# driver.net
KiCad netlist of a schematic drawn in Altium Designer
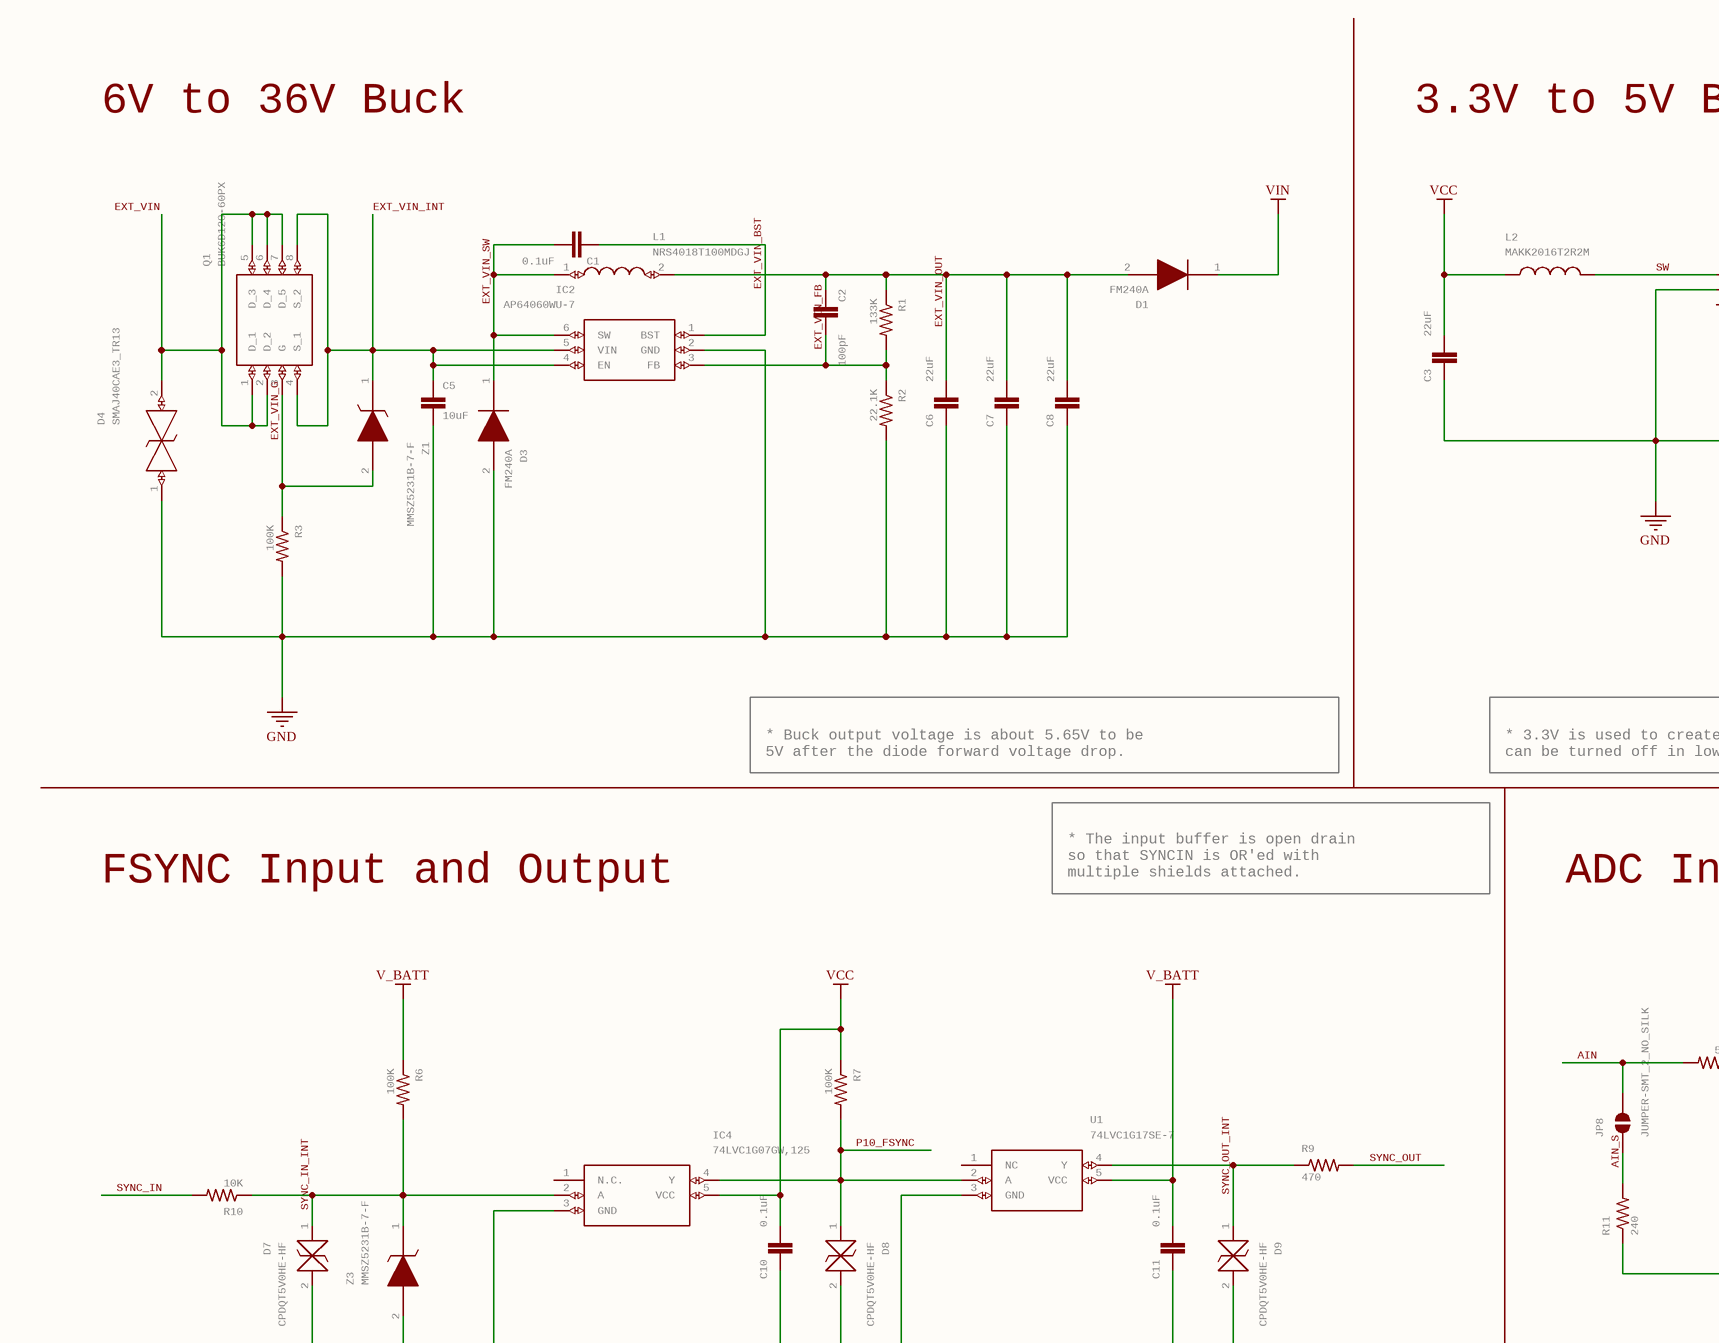
[diagram p0: driver.SchDoc, top left]
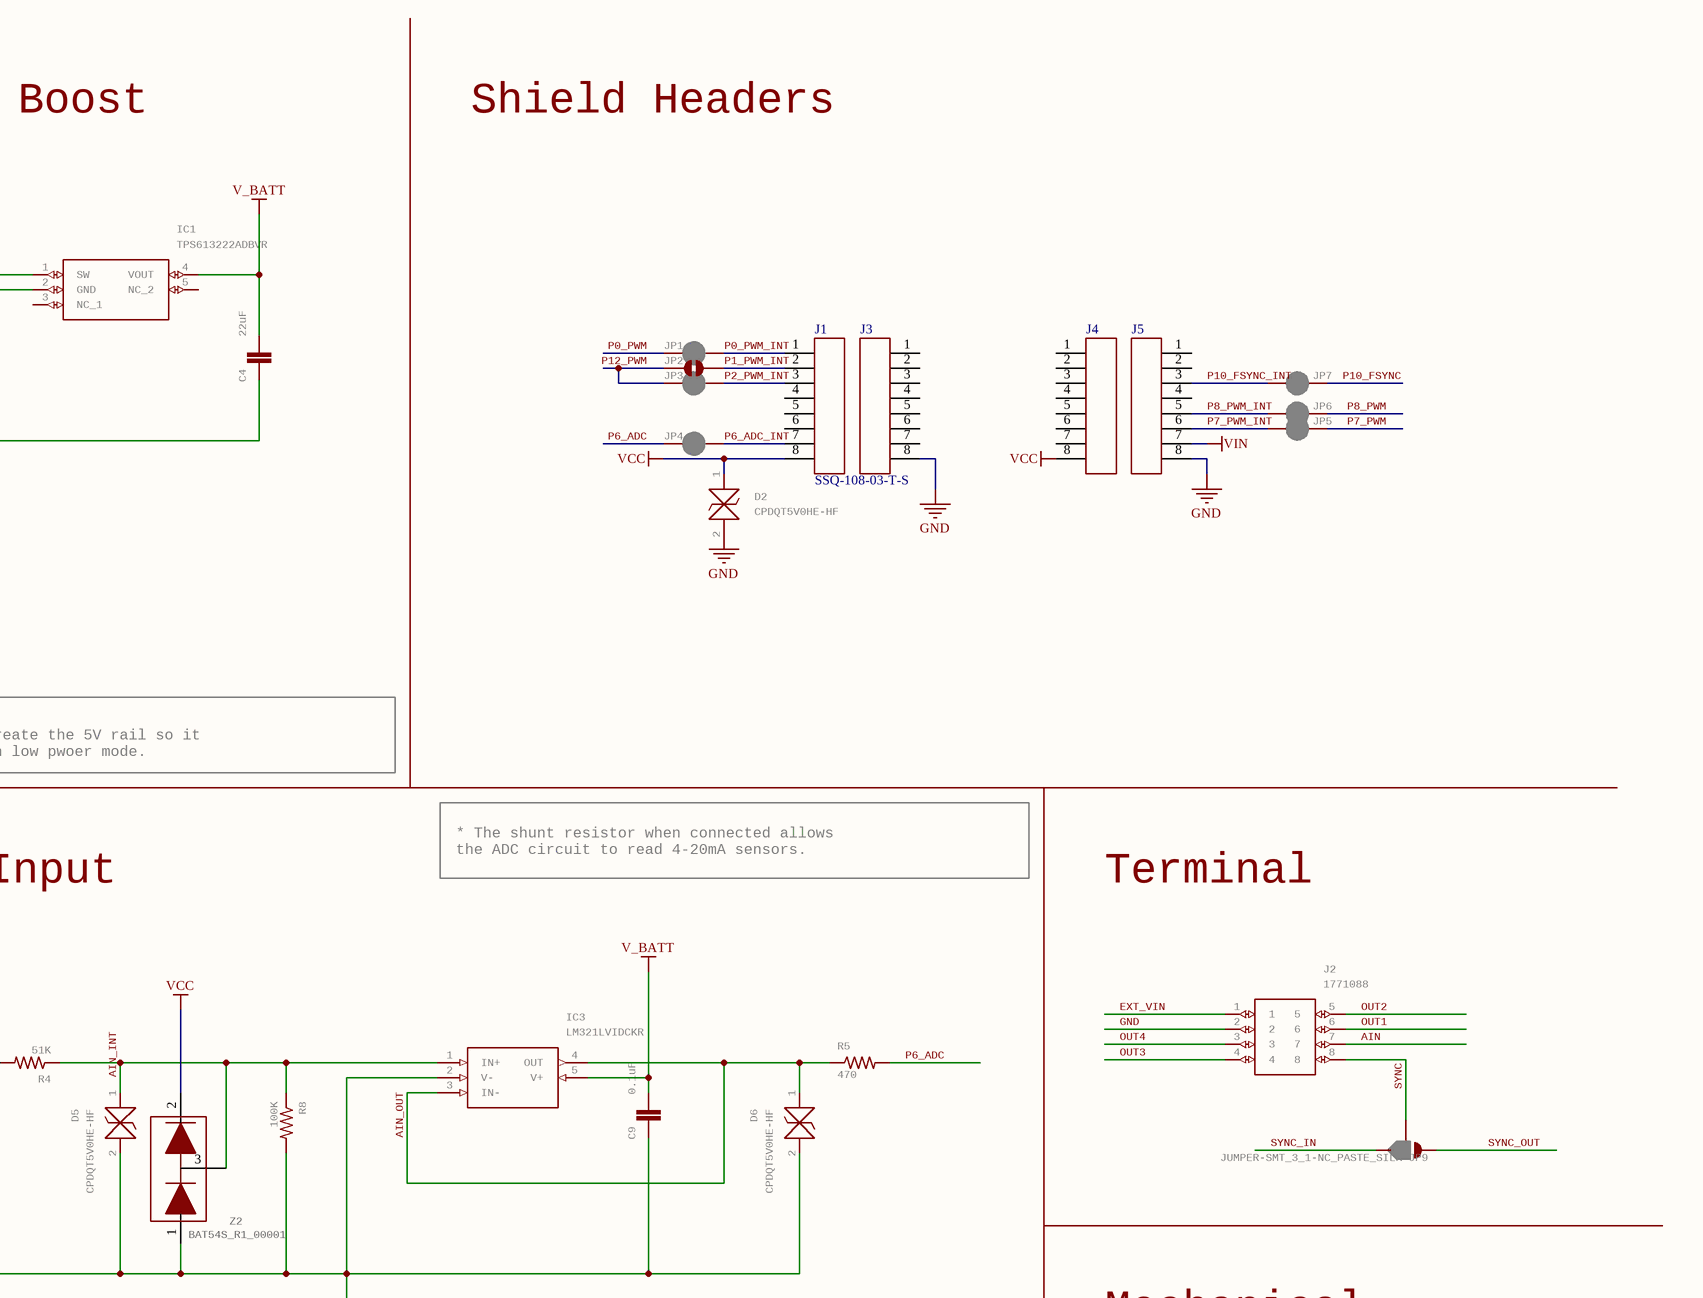
[diagram p1: driver.SchDoc, top right]
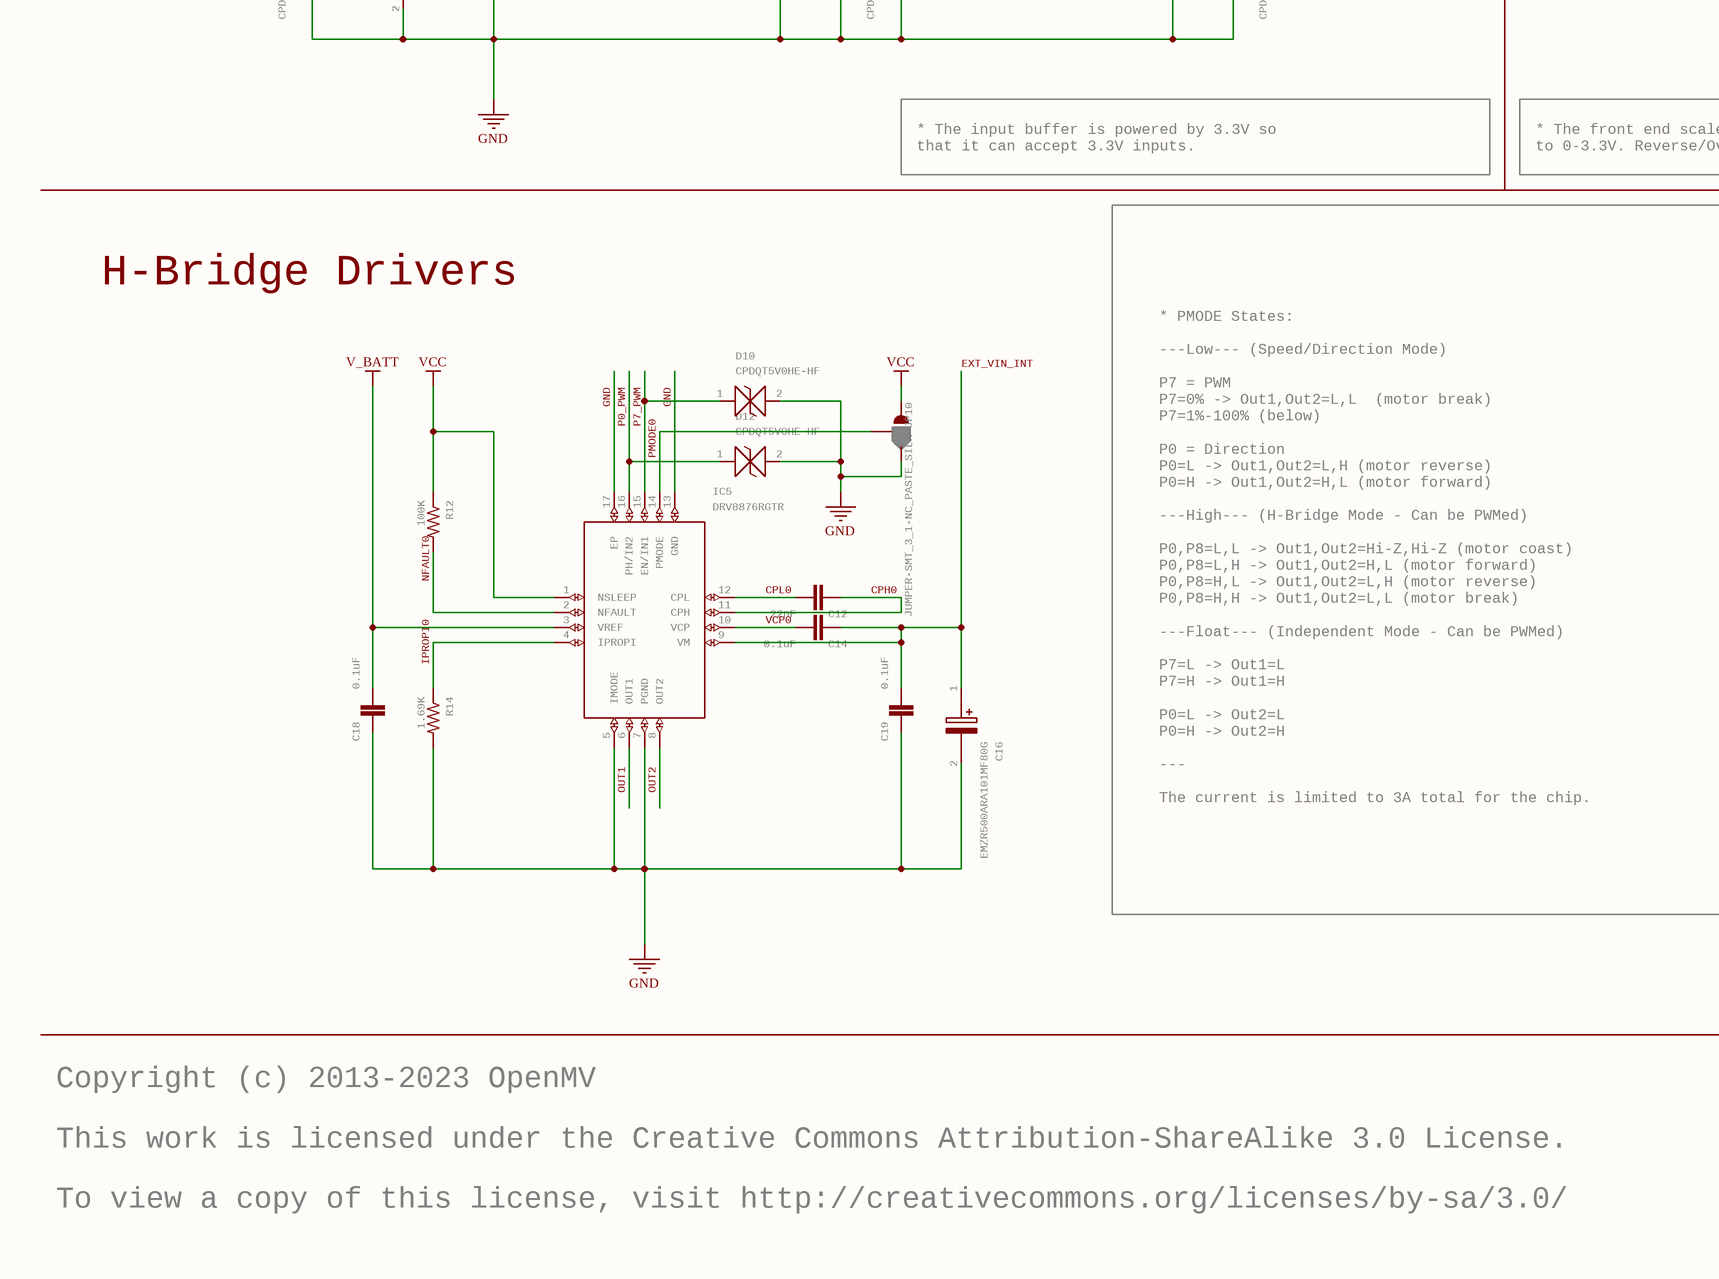
[diagram p2: driver.SchDoc, bottom left]
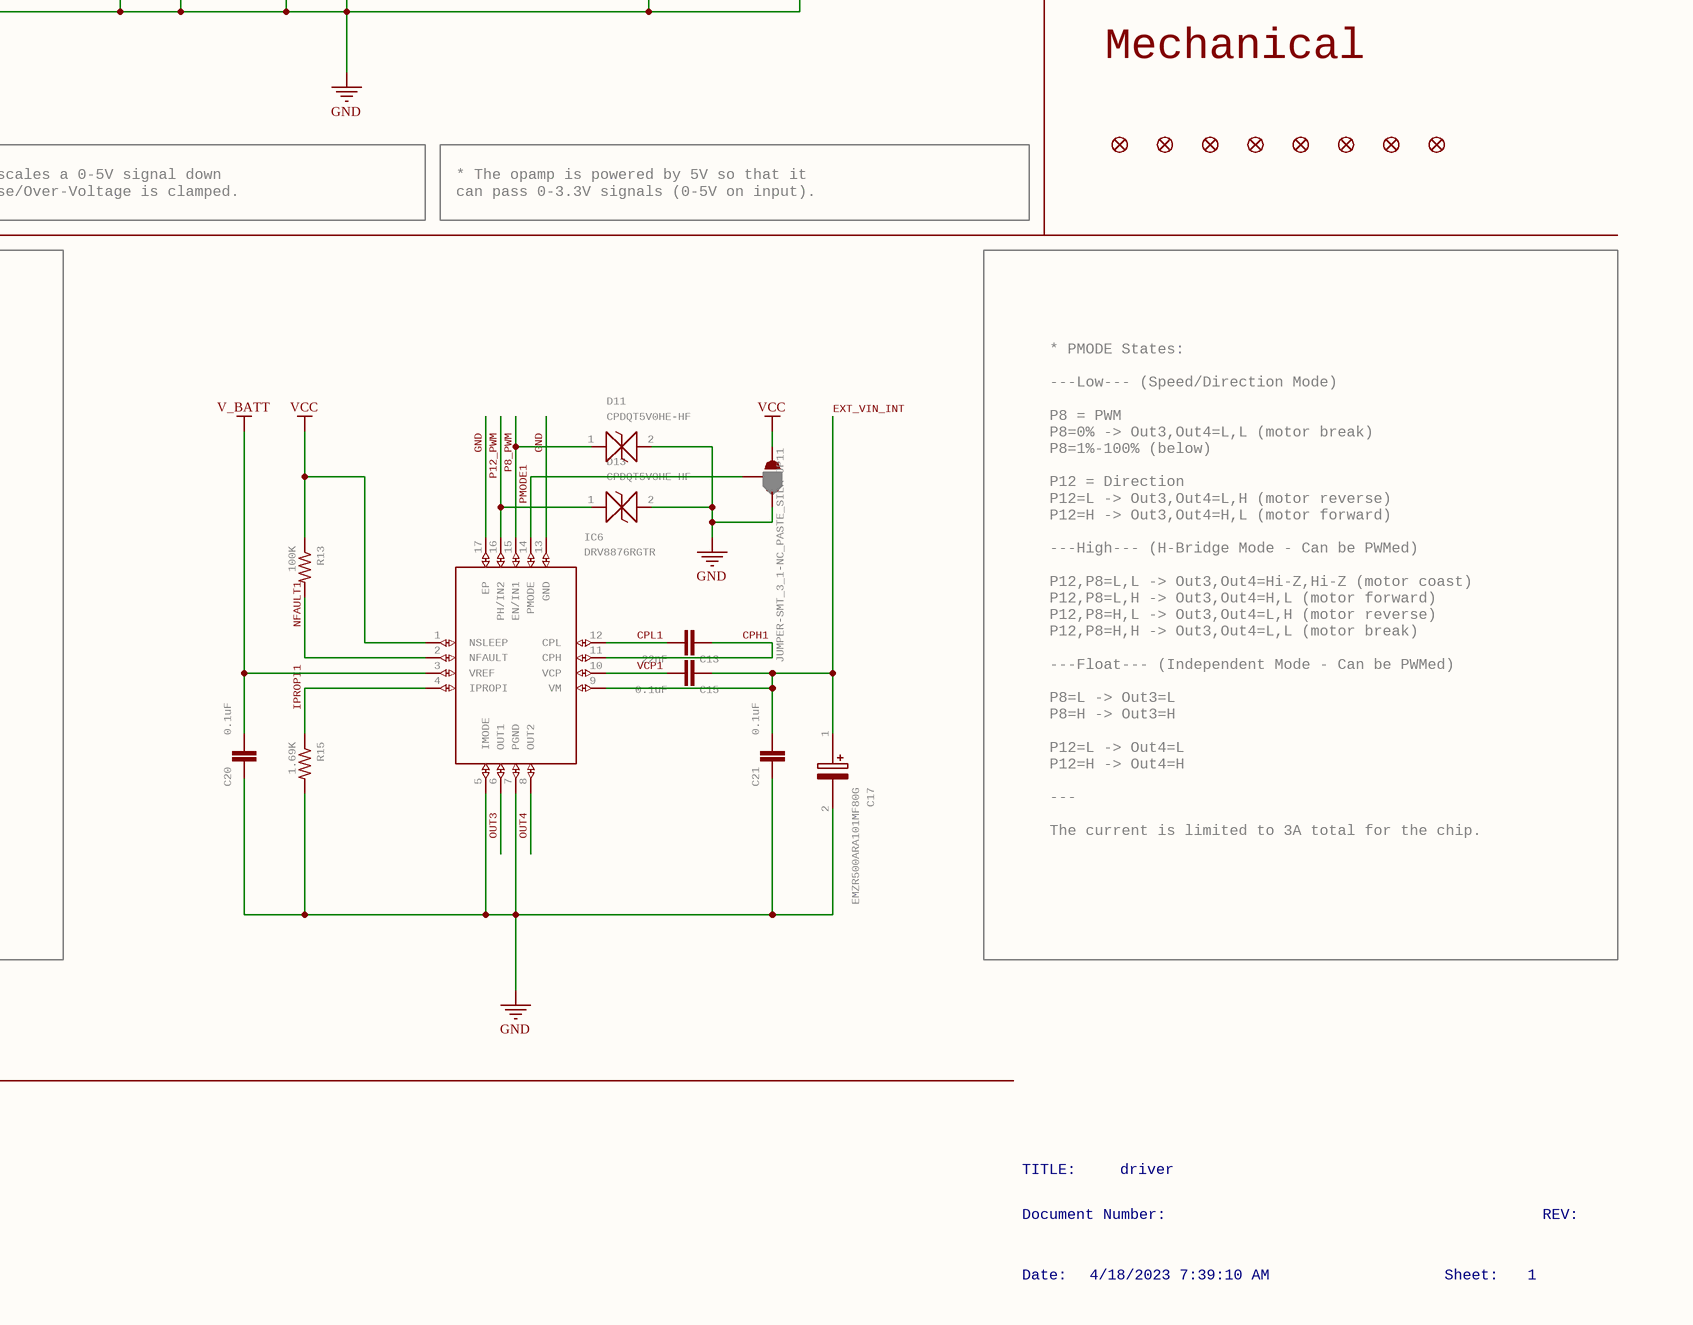
[diagram p3: driver.SchDoc, bottom right]

(export (version "E")
  (design (tool "Eeschema 10.0.6"))
  (components
    (comp (ref "C1")
      (value "0.1uF")
      (footprint "0402-CAP")
      (description "CapacitorStandard 0603 ceramic capacitor, and 0.1\" leaded capacitor.")
      (fields (field (name "MPN") "GRM155R71H104KE14D"))
      (libsource (lib "driver") (part "CAP0402-CAP"))
    )
    (comp (ref "C2")
      (value "100pF")
      (footprint "0402-CAP")
      (description "CapacitorStandard 0603 ceramic capacitor, and 0.1\" leaded capacitor.")
      (fields (field (name "MPN") "CC0402JRNPO9BN101"))
      (libsource (lib "") (part "CAP0402-CAP_2"))
    )
    (comp (ref "C3")
      (value "22uF")
      (footprint "0805")
      (fields (field (name "MPN") "CL21A226MQQNNNE"))
      (libsource (lib "driver") (part "22UF-0805-6.3V-20%"))
    )
    (comp (ref "C4")
      (value "22uF")
      (footprint "0805")
      (fields (field (name "MPN") "CL21A226MQQNNNE"))
      (libsource (lib "driver") (part "22UF-0805-6.3V-20%"))
    )
    (comp (ref "C5")
      (value "10uF")
      (footprint "C0805")
      (description "CAPACITOR, European symbol")
      (fields (field (name "MPN") "GRM21BR61H106KE43K"))
      (libsource (lib "driver") (part "C-EUC0805"))
    )
    (comp (ref "C6")
      (value "22uF")
      (footprint "0805")
      (fields (field (name "MPN") "CL21A226MQQNNNE"))
      (libsource (lib "driver") (part "22UF-0805-6.3V-20%"))
    )
    (comp (ref "C7")
      (value "22uF")
      (footprint "0805")
      (fields (field (name "MPN") "CL21A226MQQNNNE"))
      (libsource (lib "driver") (part "22UF-0805-6.3V-20%"))
    )
    (comp (ref "C8")
      (value "22uF")
      (footprint "0805")
      (fields (field (name "MPN") "CL21A226MQQNNNE"))
      (libsource (lib "driver") (part "22UF-0805-6.3V-20%"))
    )
    (comp (ref "C9")
      (value "0.1uF")
      (footprint "0402-CAP")
      (description "CapacitorStandard 0603 ceramic capacitor, and 0.1\" leaded capacitor.")
      (fields (field (name "MPN") "GRM155R71H104KE14D"))
      (libsource (lib "") (part "CAP0402-CAP_1"))
    )
    (comp (ref "C10")
      (value "0.1uF")
      (footprint "0402-CAP")
      (description "CapacitorStandard 0603 ceramic capacitor, and 0.1\" leaded capacitor.")
      (fields (field (name "MPN") "GRM155R71H104KE14D"))
      (libsource (lib "") (part "CAP0402-CAP_1"))
    )
    (comp (ref "C11")
      (value "0.1uF")
      (footprint "0402-CAP")
      (description "CapacitorStandard 0603 ceramic capacitor, and 0.1\" leaded capacitor.")
      (fields (field (name "MPN") "GRM155R71H104KE14D"))
      (libsource (lib "") (part "CAP0402-CAP_1"))
    )
    (comp (ref "C12")
      (value "22nF")
      (footprint "0402-CAP")
      (description "CapacitorStandard 0603 ceramic capacitor, and 0.1\" leaded capacitor.")
      (fields (field (name "MPN") "GRM155R71H223KA12D"))
      (libsource (lib "driver") (part "CAP0402-CAP"))
    )
    (comp (ref "C13")
      (value "22nF")
      (footprint "0402-CAP")
      (description "CapacitorStandard 0603 ceramic capacitor, and 0.1\" leaded capacitor.")
      (fields (field (name "MPN") "GRM155R71H223KA12D"))
      (libsource (lib "driver") (part "CAP0402-CAP"))
    )
    (comp (ref "C14")
      (value "0.1uF")
      (footprint "0402-CAP")
      (description "CapacitorStandard 0603 ceramic capacitor, and 0.1\" leaded capacitor.")
      (fields (field (name "MPN") "GRM155R71H104KE14D"))
      (libsource (lib "driver") (part "CAP0402-CAP"))
    )
    (comp (ref "C15")
      (value "0.1uF")
      (footprint "0402-CAP")
      (description "CapacitorStandard 0603 ceramic capacitor, and 0.1\" leaded capacitor.")
      (fields (field (name "MPN") "GRM155R71H104KE14D"))
      (libsource (lib "driver") (part "CAP0402-CAP"))
    )
    (comp (ref "C16")
      (value "EMZR500ARA101MF80G")
      (footprint "CAPAE660X820N")
      (description "Aluminum Electrolytic Capacitors - SMD 100uF 50V 20%   Source:  Datasheet")
      (fields (field (name "MOUSER_PART_NUMBER") "661-EMZR500ARA101MF8"))
      (libsource (lib "driver") (part "EMZR500ARA101MF80G"))
    )
    (comp (ref "C17")
      (value "EMZR500ARA101MF80G")
      (footprint "CAPAE660X820N")
      (description "Aluminum Electrolytic Capacitors - SMD 100uF 50V 20%   Source:  Datasheet")
      (fields (field (name "MOUSER_PART_NUMBER") "661-EMZR500ARA101MF8"))
      (libsource (lib "driver") (part "EMZR500ARA101MF80G"))
    )
    (comp (ref "C18")
      (value "0.1uF")
      (footprint "0402-CAP")
      (description "CapacitorStandard 0603 ceramic capacitor, and 0.1\" leaded capacitor.")
      (fields (field (name "MPN") "GRM155R71H104KE14D"))
      (libsource (lib "") (part "CAP0402-CAP_1"))
    )
    (comp (ref "C19")
      (value "0.1uF")
      (footprint "0402-CAP")
      (description "CapacitorStandard 0603 ceramic capacitor, and 0.1\" leaded capacitor.")
      (fields (field (name "MPN") "GRM155R71H104KE14D"))
      (libsource (lib "") (part "CAP0402-CAP_1"))
    )
    (comp (ref "C20")
      (value "0.1uF")
      (footprint "0402-CAP")
      (description "CapacitorStandard 0603 ceramic capacitor, and 0.1\" leaded capacitor.")
      (fields (field (name "MPN") "GRM155R71H104KE14D"))
      (libsource (lib "") (part "CAP0402-CAP_1"))
    )
    (comp (ref "C21")
      (value "0.1uF")
      (footprint "0402-CAP")
      (description "CapacitorStandard 0603 ceramic capacitor, and 0.1\" leaded capacitor.")
      (fields (field (name "MPN") "GRM155R71H104KE14D"))
      (libsource (lib "") (part "CAP0402-CAP_1"))
    )
    (comp (ref "D1")
      (value "FM240A")
      (footprint "DIOM5025X231N")
      (description "Diodes - General Purpose, Power, Switching GP Si Rectifier SMB,2A,40V   Source:  Datasheet")
      (fields (field (name "MOUSER_PART_NUMBER") "583-FM240A"))
      (libsource (lib "driver") (part "FM240A"))
    )
    (comp (ref "D2")
      (value "CPDQT5V0HE-HF")
      (footprint "CPDQT5V0HEHF")
      (description "ESD Suppressors / TVS Diodes DIODE ESD 5VWM 65W 0402/SOD-923F   Source:  Datasheet")
      (fields (field (name "MOUSER_PART_NUMBER") "MOUSER_PART_NUMBER"))
      (libsource (lib "driver") (part "CPDQT5V0HE-HF"))
    )
    (comp (ref "D3")
      (value "FM240A")
      (footprint "DIOM5025X231N")
      (description "Diodes - General Purpose, Power, Switching GP Si Rectifier SMB,2A,40V   Source:  Datasheet")
      (fields (field (name "MOUSER_PART_NUMBER") "583-FM240A"))
      (libsource (lib "driver") (part "FM240A"))
    )
    (comp (ref "D4")
      (value "SMAJ40CAE3_TR13")
      (footprint "SMAJ40CAE3TR13")
      (description "ESD Suppressors / TVS Diodes TVS   Source:  Datasheet")
      (fields
        (field (name "MANUFACTURER_PART_NUMBER") "SMAJ40CAe3/TR13")
        (field (name "MOUSER_PART_NUMBER") "494-SMAJ40CAE3/TR13")
      )
      (libsource (lib "driver") (part "SMAJ40CAE3_TR13"))
    )
    (comp (ref "D5")
      (value "CPDQT5V0HE-HF")
      (footprint "CPDQT5V0HEHF")
      (description "ESD Suppressors / TVS Diodes DIODE ESD 5VWM 65W 0402/SOD-923F   Source:  Datasheet")
      (fields (field (name "MOUSER_PART_NUMBER") "MOUSER_PART_NUMBER"))
      (libsource (lib "driver") (part "CPDQT5V0HE-HF"))
    )
    (comp (ref "D6")
      (value "CPDQT5V0HE-HF")
      (footprint "CPDQT5V0HEHF")
      (description "ESD Suppressors / TVS Diodes DIODE ESD 5VWM 65W 0402/SOD-923F   Source:  Datasheet")
      (fields (field (name "MOUSER_PART_NUMBER") "MOUSER_PART_NUMBER"))
      (libsource (lib "driver") (part "CPDQT5V0HE-HF"))
    )
    (comp (ref "D7")
      (value "CPDQT5V0HE-HF")
      (footprint "CPDQT5V0HEHF")
      (description "ESD Suppressors / TVS Diodes DIODE ESD 5VWM 65W 0402/SOD-923F   Source:  Datasheet")
      (fields (field (name "MOUSER_PART_NUMBER") "MOUSER_PART_NUMBER"))
      (libsource (lib "driver") (part "CPDQT5V0HE-HF"))
    )
    (comp (ref "D8")
      (value "CPDQT5V0HE-HF")
      (footprint "CPDQT5V0HEHF")
      (description "ESD Suppressors / TVS Diodes DIODE ESD 5VWM 65W 0402/SOD-923F   Source:  Datasheet")
      (fields (field (name "MOUSER_PART_NUMBER") "MOUSER_PART_NUMBER"))
      (libsource (lib "driver") (part "CPDQT5V0HE-HF"))
    )
    (comp (ref "D9")
      (value "CPDQT5V0HE-HF")
      (footprint "CPDQT5V0HEHF")
      (description "ESD Suppressors / TVS Diodes DIODE ESD 5VWM 65W 0402/SOD-923F   Source:  Datasheet")
      (fields (field (name "MOUSER_PART_NUMBER") "MOUSER_PART_NUMBER"))
      (libsource (lib "driver") (part "CPDQT5V0HE-HF"))
    )
    (comp (ref "D10")
      (value "CPDQT5V0HE-HF")
      (footprint "CPDQT5V0HEHF")
      (description "ESD Suppressors / TVS Diodes DIODE ESD 5VWM 65W 0402/SOD-923F   Source:  Datasheet")
      (fields (field (name "MOUSER_PART_NUMBER") "MOUSER_PART_NUMBER"))
      (libsource (lib "driver") (part "CPDQT5V0HE-HF"))
    )
    (comp (ref "D11")
      (value "CPDQT5V0HE-HF")
      (footprint "CPDQT5V0HEHF")
      (description "ESD Suppressors / TVS Diodes DIODE ESD 5VWM 65W 0402/SOD-923F   Source:  Datasheet")
      (fields (field (name "MOUSER_PART_NUMBER") "MOUSER_PART_NUMBER"))
      (libsource (lib "driver") (part "CPDQT5V0HE-HF"))
    )
    (comp (ref "D12")
      (value "CPDQT5V0HE-HF")
      (footprint "CPDQT5V0HEHF")
      (description "ESD Suppressors / TVS Diodes DIODE ESD 5VWM 65W 0402/SOD-923F   Source:  Datasheet")
      (fields (field (name "MOUSER_PART_NUMBER") "MOUSER_PART_NUMBER"))
      (libsource (lib "driver") (part "CPDQT5V0HE-HF"))
    )
    (comp (ref "D13")
      (value "CPDQT5V0HE-HF")
      (footprint "CPDQT5V0HEHF")
      (description "ESD Suppressors / TVS Diodes DIODE ESD 5VWM 65W 0402/SOD-923F   Source:  Datasheet")
      (fields (field (name "MOUSER_PART_NUMBER") "MOUSER_PART_NUMBER"))
      (libsource (lib "driver") (part "CPDQT5V0HE-HF"))
    )
    (comp (ref "FD1")
      (value "FIDUCIAL1X2")
      (footprint "FIDUCIAL-1X2")
      (fields (field (name "LIBRARYNAME") "SparkFun-Aesthetics"))
      (libsource (lib "driver") (part "FIDUCIAL1X2"))
    )
    (comp (ref "FD2")
      (value "FIDUCIAL1X2")
      (footprint "FIDUCIAL-1X2")
      (fields (field (name "LIBRARYNAME") "SparkFun-Aesthetics"))
      (libsource (lib "driver") (part "FIDUCIAL1X2"))
    )
    (comp (ref "FD3")
      (value "FIDUCIAL1X2")
      (footprint "FIDUCIAL-1X2")
      (fields (field (name "LIBRARYNAME") "SparkFun-Aesthetics"))
      (libsource (lib "driver") (part "FIDUCIAL1X2"))
    )
    (comp (ref "FD4")
      (value "FIDUCIAL1X2")
      (footprint "FIDUCIAL-1X2")
      (fields (field (name "LIBRARYNAME") "SparkFun-Aesthetics"))
      (libsource (lib "driver") (part "FIDUCIAL1X2"))
    )
    (comp (ref "FD5")
      (value "FIDUCIAL1X2")
      (footprint "FIDUCIAL-1X2")
      (fields (field (name "LIBRARYNAME") "SparkFun-Aesthetics"))
      (libsource (lib "driver") (part "FIDUCIAL1X2"))
    )
    (comp (ref "FD6")
      (value "FIDUCIAL1X2")
      (footprint "FIDUCIAL-1X2")
      (fields (field (name "LIBRARYNAME") "SparkFun-Aesthetics"))
      (libsource (lib "driver") (part "FIDUCIAL1X2"))
    )
    (comp (ref "FD7")
      (value "FIDUCIAL1X2")
      (footprint "FIDUCIAL-1X2")
      (fields (field (name "LIBRARYNAME") "SparkFun-Aesthetics"))
      (libsource (lib "driver") (part "FIDUCIAL1X2"))
    )
    (comp (ref "FD8")
      (value "FIDUCIAL1X2")
      (footprint "FIDUCIAL-1X2")
      (fields (field (name "LIBRARYNAME") "SparkFun-Aesthetics"))
      (libsource (lib "driver") (part "FIDUCIAL1X2"))
    )
    (comp (ref "IC1")
      (value "TPS613222ADBVR")
      (footprint "SOT95P280X145-5N")
      (description "6-uA Quiescent Current, 1.8-A Switch Current Boost Converter   Source:  Datasheet")
      (fields (field (name "MOUSER_PART_NUMBER") "595-TPS613222ADBVR"))
      (libsource (lib "driver") (part "TPS613222ADBVR"))
    )
    (comp (ref "IC2")
      (value "AP64060WU-7")
      (footprint "SOT95P280X100-6N")
      (description "Switching Voltage Regulators DCDC Conv HV Buck TSOT26(STD) T&R 3K   Source:  Datasheet")
      (fields (field (name "MOUSER_PART_NUMBER") "621-AP64060WU-7"))
      (libsource (lib "driver") (part "AP64060WU-7"))
    )
    (comp (ref "IC3")
      (value "LM321LVIDCKR")
      (footprint "SOT65P210X110-5N")
      (description "1-Channel industry standard low voltage operational amplifier   Source:  Datasheet")
      (fields (field (name "MOUSER_PART_NUMBER") "595-LM321LVIDCKR"))
      (libsource (lib "driver") (part "LM321LVIDCKR"))
    )
    (comp (ref "IC4")
      (value "74LVC1G07GW,125")
      (footprint "SOT65P212X110-5N")
      (description "74LVC1G07 - Buffer with open-drain output@en-us   Source:  Datasheet")
      (fields (field (name "MOUSER_PART_NUMBER") "771-74LVC1G07GW-G"))
      (libsource (lib "driver") (part "74LVC1G07GW,125"))
    )
    (comp (ref "IC5")
      (value "DRV8876RGTR")
      (footprint "QFN50P300X300X100-17N")
      (fields (field (name "MOUSER_PART_NUMBER") "595-DRV8876RGTR"))
      (libsource (lib "driver") (part "DRV8876RGTR"))
    )
    (comp (ref "IC6")
      (value "DRV8876RGTR")
      (footprint "QFN50P300X300X100-17N")
      (fields (field (name "MOUSER_PART_NUMBER") "595-DRV8876RGTR"))
      (libsource (lib "driver") (part "DRV8876RGTR"))
    )
    (comp (ref "J1") (value "SSQ-108-03-T-S") (footprint "HDR_1X8") (libsource (lib "pir") (part "HDR_1X8")))
    (comp (ref "J2")
      (value "1771088")
      (footprint "1771088")
      (fields (field (name "MOUSER_PART_NUMBER") "651-1771088"))
      (libsource (lib "driver") (part "1771088"))
    )
    (comp (ref "J3") (value "SSQ-108-03-T-S") (footprint "HDR_1X8") (libsource (lib "") (part "HDR_1X8_1")))
    (comp (ref "J4") (value "SSQ-108-03-T-S") (footprint "HDR_1X8") (libsource (lib "pir") (part "HDR_1X8")))
    (comp (ref "J5") (value "SSQ-108-03-T-S") (footprint "HDR_1X8") (libsource (lib "") (part "HDR_1X8_1")))
    (comp (ref "JP1")
      (value "JUMPER-SMT_2_NC_PASTE_SILK")
      (footprint "SMT-JUMPER_2_NC_PASTE_SILK")
      (libsource (lib "driver") (part "JUMPER-SMT_2_NC_PASTE_SILK"))
    )
    (comp (ref "JP2")
      (value "JUMPER-SMT_2_NO_SILK")
      (footprint "SMT-JUMPER_2_NO_SILK")
      (libsource (lib "driver") (part "JUMPER-SMT_2_NO_SILK"))
    )
    (comp (ref "JP3")
      (value "JUMPER-SMT_2_NC_PASTE_SILK")
      (footprint "SMT-JUMPER_2_NC_PASTE_SILK")
      (libsource (lib "driver") (part "JUMPER-SMT_2_NC_PASTE_SILK"))
    )
    (comp (ref "JP4")
      (value "JUMPER-SMT_2_NC_PASTE_SILK")
      (footprint "SMT-JUMPER_2_NC_PASTE_SILK")
      (libsource (lib "driver") (part "JUMPER-SMT_2_NC_PASTE_SILK"))
    )
    (comp (ref "JP5")
      (value "JUMPER-SMT_2_NC_PASTE_SILK")
      (footprint "SMT-JUMPER_2_NC_PASTE_SILK")
      (libsource (lib "driver") (part "JUMPER-SMT_2_NC_PASTE_SILK"))
    )
    (comp (ref "JP6")
      (value "JUMPER-SMT_2_NC_PASTE_SILK")
      (footprint "SMT-JUMPER_2_NC_PASTE_SILK")
      (libsource (lib "driver") (part "JUMPER-SMT_2_NC_PASTE_SILK"))
    )
    (comp (ref "JP7")
      (value "JUMPER-SMT_2_NC_PASTE_SILK")
      (footprint "SMT-JUMPER_2_NC_PASTE_SILK")
      (libsource (lib "driver") (part "JUMPER-SMT_2_NC_PASTE_SILK"))
    )
    (comp (ref "JP8")
      (value "JUMPER-SMT_2_NO_SILK")
      (footprint "SMT-JUMPER_2_NO_SILK")
      (libsource (lib "driver") (part "JUMPER-SMT_2_NO_SILK"))
    )
    (comp (ref "JP9")
      (value "JUMPER-SMT_3_1-NC_PASTE_SILK")
      (footprint "SMT-JUMPER_3_1-NC_PASTE_SILK")
      (libsource (lib "driver") (part "JUMPER-SMT_3_1-NC_PASTE_SILK"))
    )
    (comp (ref "JP10")
      (value "JUMPER-SMT_3_1-NC_PASTE_SILK")
      (footprint "SMT-JUMPER_3_1-NC_PASTE_SILK")
      (libsource (lib "") (part "JUMPER-SMT_3_1-NC_PASTE_SILK_1"))
    )
    (comp (ref "JP11")
      (value "JUMPER-SMT_3_1-NC_PASTE_SILK")
      (footprint "SMT-JUMPER_3_1-NC_PASTE_SILK")
      (libsource (lib "") (part "JUMPER-SMT_3_1-NC_PASTE_SILK_1"))
    )
    (comp (ref "L1")
      (value "NRS4018T100MDGJ")
      (footprint "NRS4018T100MDGJ")
      (description "Fixed Inductors 4018 10uH 180mOhms +/-20%Tol 1200mA   Source:  Datasheet")
      (fields (field (name "MOUSER_PART_NUMBER") "963-NRS4018T100MDGJ"))
      (libsource (lib "driver") (part "NRS4018T100MDGJ"))
    )
    (comp (ref "L2")
      (value "MAKK2016T2R2M")
      (footprint "INDC2016X100N")
      (description "INDUCTOR, METAL CORE Check availability")
      (fields (field (name "MF") "Taiyo Yuden"))
      (libsource (lib "driver") (part "MAKK2016T2R2M"))
    )
    (comp (ref "Q1")
      (value "BUK6D120-60PX")
      (footprint "BUK6D12060PX")
      (description "MOSFET 60V P-CH TRENCHMOS SOT1220   Source:  Datasheet")
      (fields (field (name "MOUSER_PART_NUMBER") "771-BUK6D120-60PX"))
      (libsource (lib "driver") (part "BUK6D120-60PX"))
    )
    (comp (ref "R1")
      (value "133K")
      (footprint "0402-RES")
      (description "ResistorBasic schematic elements and footprints for 0603, 1206, and PTH resistors.")
      (fields (field (name "MPN") "RC0402FR-07133KL"))
      (libsource (lib "driver") (part "RESISTOR0402-RES"))
    )
    (comp (ref "R2")
      (value "22.1K")
      (footprint "0402-RES")
      (description "ResistorBasic schematic elements and footprints for 0603, 1206, and PTH resistors.")
      (fields (field (name "MPN") "CR0402-FX-2212GLF"))
      (libsource (lib "driver") (part "RESISTOR0402-RES"))
    )
    (comp (ref "R3")
      (value "100K")
      (footprint "0402-RES")
      (description "ResistorBasic schematic elements and footprints for 0603, 1206, and PTH resistors.")
      (fields (field (name "MPN") "AC0402FR-07100KL"))
      (libsource (lib "driver") (part "RESISTOR0402-RES"))
    )
    (comp (ref "R4")
      (value "51K")
      (footprint "0402-RES")
      (description "ResistorBasic schematic elements and footprints for 0603, 1206, and PTH resistors.")
      (fields (field (name "MPN") "RC0402JR-0751KL"))
      (libsource (lib "driver") (part "RESISTOR0402-RES"))
    )
    (comp (ref "R5")
      (value "470")
      (footprint "R0603")
      (description "RESISTOR, American symbol")
      (fields (field (name "MPN") "CR0603-FX-4700ELF"))
      (libsource (lib "driver") (part "R-US_R0603"))
    )
    (comp (ref "R6")
      (value "100K")
      (footprint "0402-RES")
      (description "ResistorBasic schematic elements and footprints for 0603, 1206, and PTH resistors.")
      (fields (field (name "MPN") "AC0402FR-07100KL"))
      (libsource (lib "driver") (part "RESISTOR0402-RES"))
    )
    (comp (ref "R7")
      (value "100K")
      (footprint "0402-RES")
      (description "ResistorBasic schematic elements and footprints for 0603, 1206, and PTH resistors.")
      (fields (field (name "MPN") "AC0402FR-07100KL"))
      (libsource (lib "driver") (part "RESISTOR0402-RES"))
    )
    (comp (ref "R8")
      (value "100K")
      (footprint "0402-RES")
      (description "ResistorBasic schematic elements and footprints for 0603, 1206, and PTH resistors.")
      (fields (field (name "MPN") "AC0402FR-07100KL"))
      (libsource (lib "driver") (part "RESISTOR0402-RES"))
    )
    (comp (ref "R9")
      (value "470")
      (footprint "R0603")
      (description "RESISTOR, American symbol")
      (fields (field (name "MPN") "CR0603-FX-4700ELF"))
      (libsource (lib "driver") (part "R-US_R0603"))
    )
    (comp (ref "R10")
      (value "10K")
      (footprint "0402-RES")
      (description "ResistorBasic schematic elements and footprints for 0603, 1206, and PTH resistors.")
      (fields (field (name "MPN") "AC0402FR-1310KL"))
      (libsource (lib "driver") (part "RESISTOR0402-RES"))
    )
    (comp (ref "R11")
      (value "240")
      (footprint "R0603")
      (description "RESISTOR, American symbol")
      (fields (field (name "MPN") "RK73B1JTTD241J"))
      (libsource (lib "driver") (part "R-US_R0603"))
    )
    (comp (ref "R12")
      (value "100K")
      (footprint "0402-RES")
      (description "ResistorBasic schematic elements and footprints for 0603, 1206, and PTH resistors.")
      (fields (field (name "MPN") "AC0402FR-07100KL"))
      (libsource (lib "driver") (part "RESISTOR0402-RES"))
    )
    (comp (ref "R13")
      (value "100K")
      (footprint "0402-RES")
      (description "ResistorBasic schematic elements and footprints for 0603, 1206, and PTH resistors.")
      (fields (field (name "MPN") "AC0402FR-07100KL"))
      (libsource (lib "driver") (part "RESISTOR0402-RES"))
    )
    (comp (ref "R14")
      (value "1.69K")
      (footprint "0402-RES")
      (description "ResistorBasic schematic elements and footprints for 0603, 1206, and PTH resistors.")
      (fields (field (name "MPN") "RC0402FR-07169RL"))
      (libsource (lib "driver") (part "RESISTOR0402-RES"))
    )
    (comp (ref "R15")
      (value "1.69K")
      (footprint "0402-RES")
      (description "ResistorBasic schematic elements and footprints for 0603, 1206, and PTH resistors.")
      (fields (field (name "MPN") "RC0402FR-07169RL"))
      (libsource (lib "driver") (part "RESISTOR0402-RES"))
    )
    (comp (ref "U1")
      (value "74LVC1G17SE-7")
      (footprint "SOT65P210X110-5N")
      (fields (field (name "MOUSER_PART_NUMBER") "621-74LVC1G17SE-7"))
      (libsource (lib "driver") (part "74LVC1G17SE-7"))
    )
    (comp (ref "Z1")
      (value "MMSZ5231B-7-F")
      (footprint "SOD3716X145N")
      (fields (field (name "MOUSER_PART_NUMBER") "621-MMSZ5231B-F"))
      (libsource (lib "driver") (part "MMSZ5231B-7-F"))
    )
    (comp (ref "Z2")
      (value "BAT54S_R1_00001")
      (footprint "SOT23-3")
      (libsource (lib "can-rs232") (part "BAT54S_R1_00001"))
    )
    (comp (ref "Z3")
      (value "MMSZ5231B-7-F")
      (footprint "SOD3716X145N")
      (fields (field (name "MOUSER_PART_NUMBER") "621-MMSZ5231B-F"))
      (libsource (lib "driver") (part "MMSZ5231B-7-F"))
    )
  )
  (nets
    (net (code "1") (name "/AIN") (class "Default")
      (node (ref "J2") (pin "7") (pinfunction "7_7") (pintype "bidirectional"))
      (node (ref "JP8") (pin "2") (pinfunction "2_2") (pintype "passive"))
      (node (ref "R4") (pin "2") (pinfunction "2_2") (pintype "passive"))
    )
    (net (code "2") (name "/AIN_INT") (class "Default")
      (node (ref "D5") (pin "1") (pinfunction "1_1") (pintype "bidirectional"))
      (node (ref "IC3") (pin "1") (pinfunction "IN+_1") (pintype "input"))
      (node (ref "R4") (pin "1") (pinfunction "1_1") (pintype "passive"))
      (node (ref "R8") (pin "1") (pinfunction "1_1") (pintype "passive"))
      (node (ref "Z2") (pin "3") (pintype "passive"))
    )
    (net (code "3") (name "/AIN_OUT") (class "Default")
      (node (ref "D6") (pin "1") (pinfunction "1_1") (pintype "bidirectional"))
      (node (ref "IC3") (pin "3") (pinfunction "IN-_3") (pintype "input"))
      (node (ref "IC3") (pin "4") (pinfunction "OUT_4") (pintype "output"))
      (node (ref "R5") (pin "1") (pinfunction "1_1") (pintype "passive"))
    )
    (net (code "4") (name "/AIN_S") (class "Default")
      (node (ref "JP8") (pin "1") (pinfunction "1_1") (pintype "passive"))
      (node (ref "R11") (pin "2") (pinfunction "2_2") (pintype "passive"))
    )
    (net (code "5") (name "/CPH0") (class "Default")
      (node (ref "C12") (pin "1") (pinfunction "1_1") (pintype "passive"))
      (node (ref "IC5") (pin "11") (pinfunction "CPH_11") (pintype "bidirectional"))
    )
    (net (code "6") (name "/CPH1") (class "Default")
      (node (ref "C13") (pin "1") (pinfunction "1_1") (pintype "passive"))
      (node (ref "IC6") (pin "11") (pinfunction "CPH_11") (pintype "bidirectional"))
    )
    (net (code "7") (name "/CPL0") (class "Default")
      (node (ref "C12") (pin "2") (pinfunction "2_2") (pintype "passive"))
      (node (ref "IC5") (pin "12") (pinfunction "CPL_12") (pintype "bidirectional"))
    )
    (net (code "8") (name "/CPL1") (class "Default")
      (node (ref "C13") (pin "2") (pinfunction "2_2") (pintype "passive"))
      (node (ref "IC6") (pin "12") (pinfunction "CPL_12") (pintype "bidirectional"))
    )
    (net (code "9") (name "/EXT_VIN") (class "Default")
      (node (ref "D4") (pin "2") (pinfunction "2_2") (pintype "bidirectional"))
      (node (ref "J2") (pin "1") (pinfunction "1_1") (pintype "bidirectional"))
      (node (ref "Q1") (pin "1") (pinfunction "D_1_1") (pintype "bidirectional"))
      (node (ref "Q1") (pin "2") (pinfunction "D_2_2") (pintype "bidirectional"))
      (node (ref "Q1") (pin "5") (pinfunction "D_3_5") (pintype "bidirectional"))
      (node (ref "Q1") (pin "6") (pinfunction "D_4_6") (pintype "bidirectional"))
      (node (ref "Q1") (pin "7") (pinfunction "D_5_7") (pintype "bidirectional"))
    )
    (net (code "10") (name "/EXT_VIN_BST") (class "Default")
      (node (ref "C1") (pin "1") (pinfunction "1_1") (pintype "passive"))
      (node (ref "IC2") (pin "1") (pinfunction "BST_1") (pintype "bidirectional"))
    )
    (net (code "11") (name "/EXT_VIN_FB") (class "Default")
      (node (ref "C2") (pin "2") (pinfunction "2_2") (pintype "passive"))
      (node (ref "IC2") (pin "3") (pinfunction "FB_3") (pintype "bidirectional"))
      (node (ref "R1") (pin "2") (pinfunction "2_2") (pintype "passive"))
      (node (ref "R2") (pin "1") (pinfunction "1_1") (pintype "passive"))
    )
    (net (code "12") (name "/EXT_VIN_G") (class "Default")
      (node (ref "Q1") (pin "3") (pinfunction "G_3") (pintype "bidirectional"))
      (node (ref "R3") (pin "1") (pinfunction "1_1") (pintype "passive"))
      (node (ref "Z1") (pin "2") (pinfunction "A_2") (pintype "bidirectional"))
    )
    (net (code "13") (name "/EXT_VIN_INT") (class "Default")
      (node (ref "C14") (pin "1") (pinfunction "1_1") (pintype "passive"))
      (node (ref "C15") (pin "1") (pinfunction "1_1") (pintype "passive"))
      (node (ref "C16") (pin "1") (pinfunction "+_1") (pintype "bidirectional"))
      (node (ref "C17") (pin "1") (pinfunction "+_1") (pintype "bidirectional"))
      (node (ref "C19") (pin "2") (pinfunction "2_2") (pintype "passive"))
      (node (ref "C21") (pin "2") (pinfunction "2_2") (pintype "passive"))
      (node (ref "C5") (pin "1") (pinfunction "1_1") (pintype "passive"))
      (node (ref "IC2") (pin "4") (pinfunction "EN_4") (pintype "bidirectional"))
      (node (ref "IC2") (pin "5") (pinfunction "VIN_5") (pintype "bidirectional"))
      (node (ref "IC5") (pin "9") (pinfunction "VM_9") (pintype "bidirectional"))
      (node (ref "IC6") (pin "9") (pinfunction "VM_9") (pintype "bidirectional"))
      (node (ref "Q1") (pin "4") (pinfunction "S_1_4") (pintype "bidirectional"))
      (node (ref "Q1") (pin "8") (pinfunction "S_2_8") (pintype "bidirectional"))
      (node (ref "Z1") (pin "1") (pinfunction "K_1") (pintype "bidirectional"))
    )
    (net (code "14") (name "/EXT_VIN_OUT") (class "Default")
      (node (ref "C2") (pin "1") (pinfunction "1_1") (pintype "passive"))
      (node (ref "C6") (pin "2") (pinfunction "2_2") (pintype "passive"))
      (node (ref "C7") (pin "2") (pinfunction "2_2") (pintype "passive"))
      (node (ref "C8") (pin "2") (pinfunction "2_2") (pintype "passive"))
      (node (ref "D1") (pin "2") (pinfunction "A_2") (pintype "bidirectional"))
      (node (ref "L1") (pin "2") (pinfunction "2_2") (pintype "bidirectional"))
      (node (ref "R1") (pin "1") (pinfunction "1_1") (pintype "passive"))
    )
    (net (code "15") (name "/EXT_VIN_SW") (class "Default")
      (node (ref "C1") (pin "2") (pinfunction "2_2") (pintype "passive"))
      (node (ref "D3") (pin "1") (pinfunction "K_1") (pintype "bidirectional"))
      (node (ref "IC2") (pin "6") (pinfunction "SW_6") (pintype "bidirectional"))
      (node (ref "L1") (pin "1") (pinfunction "1_1") (pintype "bidirectional"))
    )
    (net (code "16") (name "/IPROPI0") (class "Default")
      (node (ref "IC5") (pin "4") (pinfunction "IPROPI_4") (pintype "bidirectional"))
      (node (ref "R14") (pin "1") (pinfunction "1_1") (pintype "passive"))
    )
    (net (code "17") (name "/IPROPI1") (class "Default")
      (node (ref "IC6") (pin "4") (pinfunction "IPROPI_4") (pintype "bidirectional"))
      (node (ref "R15") (pin "1") (pinfunction "1_1") (pintype "passive"))
    )
    (net (code "18") (name "/NFAULT0") (class "Default")
      (node (ref "IC5") (pin "2") (pinfunction "NFAULT_2") (pintype "bidirectional"))
      (node (ref "R12") (pin "2") (pinfunction "2_2") (pintype "passive"))
    )
    (net (code "19") (name "/NFAULT1") (class "Default")
      (node (ref "IC6") (pin "2") (pinfunction "NFAULT_2") (pintype "bidirectional"))
      (node (ref "R13") (pin "2") (pinfunction "2_2") (pintype "passive"))
    )
    (net (code "20") (name "/OUT1") (class "Default")
      (node (ref "IC5") (pin "6") (pinfunction "OUT1_6") (pintype "bidirectional"))
      (node (ref "J2") (pin "6") (pinfunction "6_6") (pintype "bidirectional"))
    )
    (net (code "21") (name "/OUT2") (class "Default")
      (node (ref "IC5") (pin "8") (pinfunction "OUT2_8") (pintype "bidirectional"))
      (node (ref "J2") (pin "5") (pinfunction "5_5") (pintype "bidirectional"))
    )
    (net (code "22") (name "/OUT3") (class "Default")
      (node (ref "IC6") (pin "6") (pinfunction "OUT1_6") (pintype "bidirectional"))
      (node (ref "J2") (pin "4") (pinfunction "4_4") (pintype "bidirectional"))
    )
    (net (code "23") (name "/OUT4") (class "Default")
      (node (ref "IC6") (pin "8") (pinfunction "OUT2_8") (pintype "bidirectional"))
      (node (ref "J2") (pin "3") (pinfunction "3_3") (pintype "bidirectional"))
    )
    (net (code "24") (name "/P0_PWM") (class "Default")
      (node (ref "D12") (pin "1") (pinfunction "1_1") (pintype "bidirectional"))
      (node (ref "IC5") (pin "16") (pinfunction "PH/IN2_16") (pintype "bidirectional"))
      (node (ref "JP1") (pin "2") (pinfunction "2_2") (pintype "passive"))
    )
    (net (code "25") (name "/P0_PWM_INT") (class "Default")
      (node (ref "J1") (pin "1") (pintype "passive"))
      (node (ref "JP1") (pin "1") (pinfunction "1_1") (pintype "passive"))
    )
    (net (code "26") (name "/P1_PWM_INT") (class "Default")
      (node (ref "J1") (pin "2") (pintype "passive"))
      (node (ref "JP2") (pin "1") (pinfunction "1_1") (pintype "passive"))
    )
    (net (code "27") (name "/P2_PWM_INT") (class "Default")
      (node (ref "J1") (pin "3") (pintype "passive"))
      (node (ref "JP3") (pin "1") (pinfunction "1_1") (pintype "passive"))
    )
    (net (code "28") (name "/P6_ADC") (class "Default")
      (node (ref "JP4") (pin "2") (pinfunction "2_2") (pintype "passive"))
      (node (ref "R5") (pin "2") (pinfunction "2_2") (pintype "passive"))
    )
    (net (code "29") (name "/P6_ADC_INT") (class "Default")
      (node (ref "J1") (pin "7") (pintype "passive"))
      (node (ref "JP4") (pin "1") (pinfunction "1_1") (pintype "passive"))
    )
    (net (code "30") (name "/P7_PWM") (class "Default")
      (node (ref "D10") (pin "1") (pinfunction "1_1") (pintype "bidirectional"))
      (node (ref "IC5") (pin "15") (pinfunction "EN/IN1_15") (pintype "bidirectional"))
      (node (ref "JP5") (pin "2") (pinfunction "2_2") (pintype "passive"))
    )
    (net (code "31") (name "/P7_PWM_INT") (class "Default")
      (node (ref "J5") (pin "6") (pintype "passive"))
      (node (ref "JP5") (pin "1") (pinfunction "1_1") (pintype "passive"))
    )
    (net (code "32") (name "/P8_PWM") (class "Default")
      (node (ref "D11") (pin "1") (pinfunction "1_1") (pintype "bidirectional"))
      (node (ref "IC6") (pin "15") (pinfunction "EN/IN1_15") (pintype "bidirectional"))
      (node (ref "JP6") (pin "2") (pinfunction "2_2") (pintype "passive"))
    )
    (net (code "33") (name "/P8_PWM_INT") (class "Default")
      (node (ref "J5") (pin "5") (pintype "passive"))
      (node (ref "JP6") (pin "1") (pinfunction "1_1") (pintype "passive"))
    )
    (net (code "34") (name "/P10_FSYNC") (class "Default")
      (node (ref "D8") (pin "1") (pinfunction "1_1") (pintype "bidirectional"))
      (node (ref "IC4") (pin "4") (pinfunction "Y_4") (pintype "bidirectional"))
      (node (ref "JP7") (pin "2") (pinfunction "2_2") (pintype "passive"))
      (node (ref "R7") (pin "2") (pinfunction "2_2") (pintype "passive"))
      (node (ref "U1") (pin "2") (pinfunction "A_2") (pintype "bidirectional"))
    )
    (net (code "35") (name "/P10_FSYNC_INT") (class "Default")
      (node (ref "J5") (pin "3") (pintype "passive"))
      (node (ref "JP7") (pin "1") (pinfunction "1_1") (pintype "passive"))
    )
    (net (code "36") (name "/P12_PWM") (class "Default")
      (node (ref "D13") (pin "1") (pinfunction "1_1") (pintype "bidirectional"))
      (node (ref "IC6") (pin "16") (pinfunction "PH/IN2_16") (pintype "bidirectional"))
      (node (ref "JP2") (pin "2") (pinfunction "2_2") (pintype "passive"))
      (node (ref "JP3") (pin "2") (pinfunction "2_2") (pintype "passive"))
    )
    (net (code "37") (name "/PMODE0") (class "Default")
      (node (ref "IC5") (pin "14") (pinfunction "PMODE_14") (pintype "bidirectional"))
      (node (ref "JP10") (pin "2") (pinfunction "2_2") (pintype "passive"))
    )
    (net (code "38") (name "/PMODE1") (class "Default")
      (node (ref "IC6") (pin "14") (pinfunction "PMODE_14") (pintype "bidirectional"))
      (node (ref "JP11") (pin "2") (pinfunction "2_2") (pintype "passive"))
    )
    (net (code "39") (name "/SW") (class "Default")
      (node (ref "IC1") (pin "1") (pinfunction "SW_1") (pintype "bidirectional"))
      (node (ref "L2") (pin "2") (pinfunction "2_2") (pintype "passive"))
    )
    (net (code "40") (name "/SYNC") (class "Default")
      (node (ref "J2") (pin "8") (pinfunction "8_8") (pintype "bidirectional"))
      (node (ref "JP9") (pin "2") (pinfunction "2_2") (pintype "passive"))
    )
    (net (code "41") (name "/SYNC_IN") (class "Default")
      (node (ref "JP9") (pin "3") (pinfunction "3_3") (pintype "passive"))
      (node (ref "R10") (pin "2") (pinfunction "2_2") (pintype "passive"))
    )
    (net (code "42") (name "/SYNC_IN_INT") (class "Default")
      (node (ref "D7") (pin "1") (pinfunction "1_1") (pintype "bidirectional"))
      (node (ref "IC4") (pin "2") (pinfunction "A_2") (pintype "bidirectional"))
      (node (ref "R10") (pin "1") (pinfunction "1_1") (pintype "passive"))
      (node (ref "R6") (pin "2") (pinfunction "2_2") (pintype "passive"))
      (node (ref "Z3") (pin "1") (pinfunction "K_1") (pintype "bidirectional"))
    )
    (net (code "43") (name "/SYNC_OUT") (class "Default")
      (node (ref "JP9") (pin "1") (pinfunction "1_1") (pintype "passive"))
      (node (ref "R9") (pin "2") (pinfunction "2_2") (pintype "passive"))
    )
    (net (code "44") (name "/SYNC_OUT_INT") (class "Default")
      (node (ref "D9") (pin "1") (pinfunction "1_1") (pintype "bidirectional"))
      (node (ref "R9") (pin "1") (pinfunction "1_1") (pintype "passive"))
      (node (ref "U1") (pin "4") (pinfunction "Y_4") (pintype "bidirectional"))
    )
    (net (code "45") (name "/VCP0") (class "Default")
      (node (ref "C14") (pin "2") (pinfunction "2_2") (pintype "passive"))
      (node (ref "IC5") (pin "10") (pinfunction "VCP_10") (pintype "bidirectional"))
    )
    (net (code "46") (name "/VCP1") (class "Default")
      (node (ref "C15") (pin "2") (pinfunction "2_2") (pintype "passive"))
      (node (ref "IC6") (pin "10") (pinfunction "VCP_10") (pintype "bidirectional"))
    )
    (net (code "47") (name "GND") (class "Default")
      (node (ref "C10") (pin "1") (pinfunction "1_1") (pintype "passive"))
      (node (ref "C11") (pin "1") (pinfunction "1_1") (pintype "passive"))
      (node (ref "C16") (pin "2") (pinfunction "-_2") (pintype "bidirectional"))
      (node (ref "C17") (pin "2") (pinfunction "-_2") (pintype "bidirectional"))
      (node (ref "C18") (pin "1") (pinfunction "1_1") (pintype "passive"))
      (node (ref "C19") (pin "1") (pinfunction "1_1") (pintype "passive"))
      (node (ref "C20") (pin "1") (pinfunction "1_1") (pintype "passive"))
      (node (ref "C21") (pin "1") (pinfunction "1_1") (pintype "passive"))
      (node (ref "C3") (pin "1") (pinfunction "1_1") (pintype "passive"))
      (node (ref "C4") (pin "1") (pinfunction "1_1") (pintype "passive"))
      (node (ref "C5") (pin "2") (pinfunction "2_2") (pintype "passive"))
      (node (ref "C6") (pin "1") (pinfunction "1_1") (pintype "passive"))
      (node (ref "C7") (pin "1") (pinfunction "1_1") (pintype "passive"))
      (node (ref "C8") (pin "1") (pinfunction "1_1") (pintype "passive"))
      (node (ref "C9") (pin "1") (pinfunction "1_1") (pintype "passive"))
      (node (ref "D10") (pin "2") (pinfunction "2_2") (pintype "bidirectional"))
      (node (ref "D11") (pin "2") (pinfunction "2_2") (pintype "bidirectional"))
      (node (ref "D12") (pin "2") (pinfunction "2_2") (pintype "bidirectional"))
      (node (ref "D13") (pin "2") (pinfunction "2_2") (pintype "bidirectional"))
      (node (ref "D2") (pin "2") (pinfunction "2_2") (pintype "bidirectional"))
      (node (ref "D3") (pin "2") (pinfunction "A_2") (pintype "bidirectional"))
      (node (ref "D4") (pin "1") (pinfunction "1_1") (pintype "bidirectional"))
      (node (ref "D5") (pin "2") (pinfunction "2_2") (pintype "bidirectional"))
      (node (ref "D6") (pin "2") (pinfunction "2_2") (pintype "bidirectional"))
      (node (ref "D7") (pin "2") (pinfunction "2_2") (pintype "bidirectional"))
      (node (ref "D8") (pin "2") (pinfunction "2_2") (pintype "bidirectional"))
      (node (ref "D9") (pin "2") (pinfunction "2_2") (pintype "bidirectional"))
      (node (ref "IC1") (pin "2") (pinfunction "GND_2") (pintype "bidirectional"))
      (node (ref "IC2") (pin "2") (pinfunction "GND_2") (pintype "bidirectional"))
      (node (ref "IC3") (pin "2") (pinfunction "V-_2") (pintype "input"))
      (node (ref "IC4") (pin "3") (pinfunction "GND_3") (pintype "bidirectional"))
      (node (ref "IC5") (pin "13") (pinfunction "GND_13") (pintype "bidirectional"))
      (node (ref "IC5") (pin "17") (pinfunction "EP_17") (pintype "bidirectional"))
      (node (ref "IC5") (pin "5") (pinfunction "IMODE_5") (pintype "bidirectional"))
      (node (ref "IC5") (pin "7") (pinfunction "PGND_7") (pintype "bidirectional"))
      (node (ref "IC6") (pin "13") (pinfunction "GND_13") (pintype "bidirectional"))
      (node (ref "IC6") (pin "17") (pinfunction "EP_17") (pintype "bidirectional"))
      (node (ref "IC6") (pin "5") (pinfunction "IMODE_5") (pintype "bidirectional"))
      (node (ref "IC6") (pin "7") (pinfunction "PGND_7") (pintype "bidirectional"))
      (node (ref "J2") (pin "2") (pinfunction "2_2") (pintype "bidirectional"))
      (node (ref "J3") (pin "8") (pintype "passive"))
      (node (ref "J5") (pin "8") (pintype "passive"))
      (node (ref "JP10") (pin "3") (pinfunction "3_3") (pintype "passive"))
      (node (ref "JP11") (pin "3") (pinfunction "3_3") (pintype "passive"))
      (node (ref "R11") (pin "1") (pinfunction "1_1") (pintype "passive"))
      (node (ref "R14") (pin "2") (pinfunction "2_2") (pintype "passive"))
      (node (ref "R15") (pin "2") (pinfunction "2_2") (pintype "passive"))
      (node (ref "R2") (pin "2") (pinfunction "2_2") (pintype "passive"))
      (node (ref "R3") (pin "2") (pinfunction "2_2") (pintype "passive"))
      (node (ref "R8") (pin "2") (pinfunction "2_2") (pintype "passive"))
      (node (ref "U1") (pin "3") (pinfunction "GND_3") (pintype "bidirectional"))
      (node (ref "Z2") (pin "1") (pintype "passive"))
      (node (ref "Z3") (pin "2") (pinfunction "A_2") (pintype "bidirectional"))
    )
    (net (code "48") (name "VCC") (class "Default")
      (node (ref "C10") (pin "2") (pinfunction "2_2") (pintype "passive"))
      (node (ref "C3") (pin "2") (pinfunction "2_2") (pintype "passive"))
      (node (ref "D2") (pin "1") (pinfunction "1_1") (pintype "bidirectional"))
      (node (ref "IC4") (pin "5") (pinfunction "VCC_5") (pintype "bidirectional"))
      (node (ref "IC5") (pin "1") (pinfunction "NSLEEP_1") (pintype "bidirectional"))
      (node (ref "IC6") (pin "1") (pinfunction "NSLEEP_1") (pintype "bidirectional"))
      (node (ref "J1") (pin "8") (pintype "passive"))
      (node (ref "J4") (pin "8") (pintype "passive"))
      (node (ref "JP10") (pin "1") (pinfunction "1_1") (pintype "passive"))
      (node (ref "JP11") (pin "1") (pinfunction "1_1") (pintype "passive"))
      (node (ref "L2") (pin "1") (pinfunction "1_1") (pintype "passive"))
      (node (ref "R12") (pin "1") (pinfunction "1_1") (pintype "passive"))
      (node (ref "R13") (pin "1") (pinfunction "1_1") (pintype "passive"))
      (node (ref "R7") (pin "1") (pinfunction "1_1") (pintype "passive"))
      (node (ref "Z2") (pin "2") (pintype "passive"))
    )
    (net (code "49") (name "VIN") (class "Default")
      (node (ref "D1") (pin "1") (pinfunction "K_1") (pintype "bidirectional"))
      (node (ref "J5") (pin "7") (pintype "passive"))
    )
    (net (code "50") (name "V_BATT") (class "Default")
      (node (ref "C11") (pin "2") (pinfunction "2_2") (pintype "passive"))
      (node (ref "C18") (pin "2") (pinfunction "2_2") (pintype "passive"))
      (node (ref "C20") (pin "2") (pinfunction "2_2") (pintype "passive"))
      (node (ref "C4") (pin "2") (pinfunction "2_2") (pintype "passive"))
      (node (ref "C9") (pin "2") (pinfunction "2_2") (pintype "passive"))
      (node (ref "IC1") (pin "4") (pinfunction "VOUT_4") (pintype "bidirectional"))
      (node (ref "IC3") (pin "5") (pinfunction "V+_5") (pintype "input"))
      (node (ref "IC5") (pin "3") (pinfunction "VREF_3") (pintype "bidirectional"))
      (node (ref "IC6") (pin "3") (pinfunction "VREF_3") (pintype "bidirectional"))
      (node (ref "R6") (pin "1") (pinfunction "1_1") (pintype "passive"))
      (node (ref "U1") (pin "5") (pinfunction "VCC_5") (pintype "bidirectional"))
    )
    (net (code "51") (name "unconnected-(IC1-NC_1-Pad3)") (class "Default")
      (node (ref "IC1") (pin "3") (pinfunction "NC_1_3") (pintype "bidirectional"))
    )
    (net (code "52") (name "unconnected-(IC1-NC_2-Pad5)") (class "Default")
      (node (ref "IC1") (pin "5") (pinfunction "NC_2_5") (pintype "bidirectional"))
    )
    (net (code "53") (name "unconnected-(IC4-N.C.-Pad1)") (class "Default")
      (node (ref "IC4") (pin "1") (pinfunction "N.C._1") (pintype "passive"))
    )
    (net (code "54") (name "unconnected-(J1-Pad4)") (class "Default")
      (node (ref "J1") (pin "4") (pintype "passive"))
    )
    (net (code "55") (name "unconnected-(J1-Pad5)") (class "Default")
      (node (ref "J1") (pin "5") (pintype "passive"))
    )
    (net (code "56") (name "unconnected-(J1-Pad6)") (class "Default")
      (node (ref "J1") (pin "6") (pintype "passive"))
    )
    (net (code "57") (name "unconnected-(J3-Pad1)") (class "Default")
      (node (ref "J3") (pin "1") (pintype "passive"))
    )
    (net (code "58") (name "unconnected-(J3-Pad2)") (class "Default")
      (node (ref "J3") (pin "2") (pintype "passive"))
    )
    (net (code "59") (name "unconnected-(J3-Pad3)") (class "Default")
      (node (ref "J3") (pin "3") (pintype "passive"))
    )
    (net (code "60") (name "unconnected-(J3-Pad4)") (class "Default")
      (node (ref "J3") (pin "4") (pintype "passive"))
    )
    (net (code "61") (name "unconnected-(J3-Pad5)") (class "Default")
      (node (ref "J3") (pin "5") (pintype "passive"))
    )
    (net (code "62") (name "unconnected-(J3-Pad6)") (class "Default")
      (node (ref "J3") (pin "6") (pintype "passive"))
    )
    (net (code "63") (name "unconnected-(J3-Pad7)") (class "Default")
      (node (ref "J3") (pin "7") (pintype "passive"))
    )
    (net (code "64") (name "unconnected-(J4-Pad1)") (class "Default")
      (node (ref "J4") (pin "1") (pintype "passive"))
    )
    (net (code "65") (name "unconnected-(J4-Pad2)") (class "Default")
      (node (ref "J4") (pin "2") (pintype "passive"))
    )
    (net (code "66") (name "unconnected-(J4-Pad3)") (class "Default")
      (node (ref "J4") (pin "3") (pintype "passive"))
    )
    (net (code "67") (name "unconnected-(J4-Pad4)") (class "Default")
      (node (ref "J4") (pin "4") (pintype "passive"))
    )
    (net (code "68") (name "unconnected-(J4-Pad5)") (class "Default")
      (node (ref "J4") (pin "5") (pintype "passive"))
    )
    (net (code "69") (name "unconnected-(J4-Pad6)") (class "Default")
      (node (ref "J4") (pin "6") (pintype "passive"))
    )
    (net (code "70") (name "unconnected-(J4-Pad7)") (class "Default")
      (node (ref "J4") (pin "7") (pintype "passive"))
    )
    (net (code "71") (name "unconnected-(J5-Pad1)") (class "Default")
      (node (ref "J5") (pin "1") (pintype "passive"))
    )
    (net (code "72") (name "unconnected-(J5-Pad2)") (class "Default")
      (node (ref "J5") (pin "2") (pintype "passive"))
    )
    (net (code "73") (name "unconnected-(J5-Pad4)") (class "Default")
      (node (ref "J5") (pin "4") (pintype "passive"))
    )
    (net (code "74") (name "unconnected-(U1-NC-Pad1)") (class "Default")
      (node (ref "U1") (pin "1") (pinfunction "NC_1") (pintype "passive"))
    )
  )
)
